# W511X.net
KiCad netlist of a schematic drawn in EAGLE
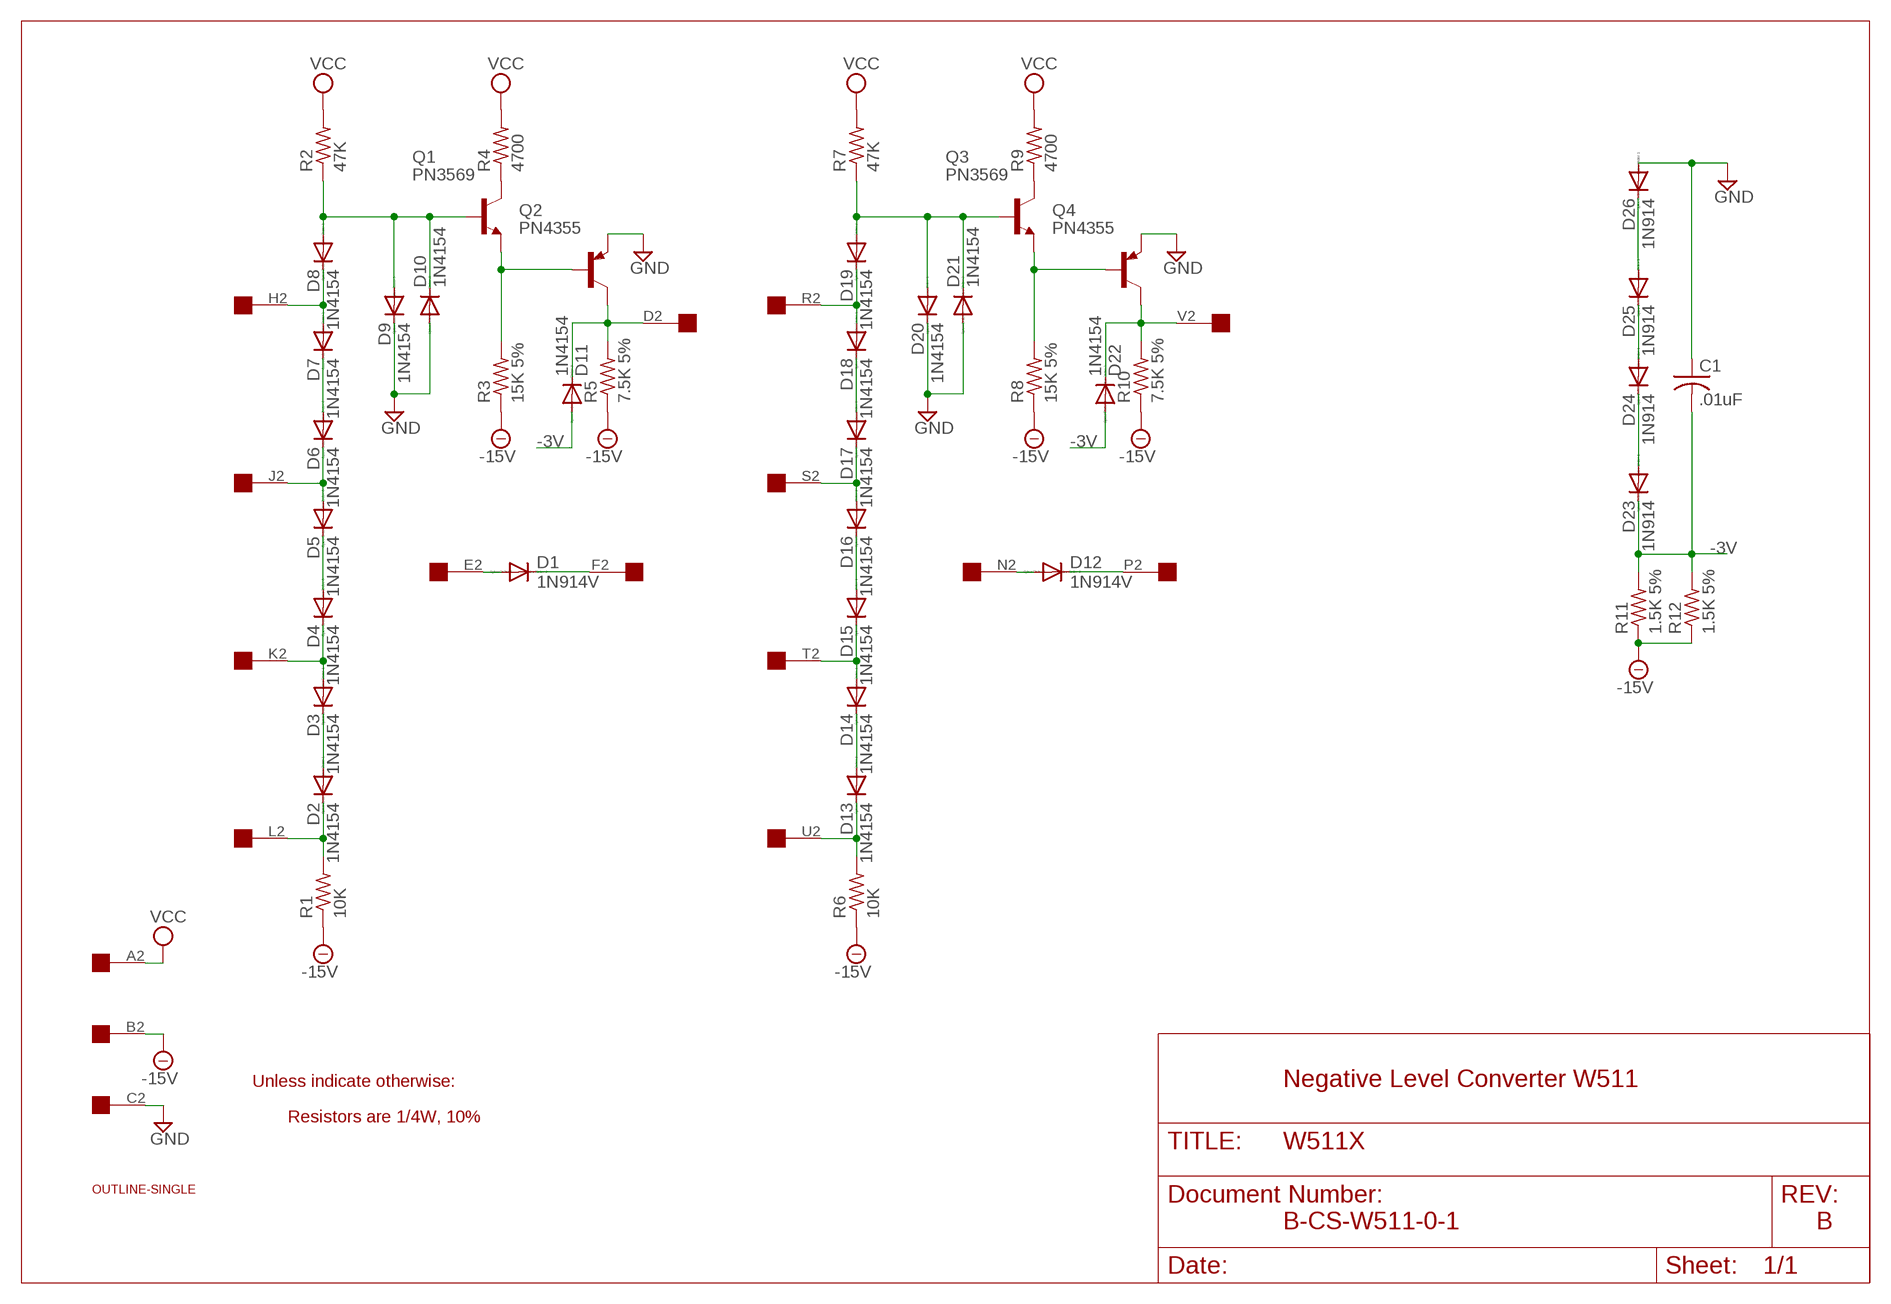
[diagram p0: schematic, sheet 1]

(export (version "E")
  (design (tool "Eeschema 10.0.6"))
  (components
    (comp (ref "C1")
      (value ".01uF")
      (footprint "eagle-import:C050-025X075")
      (libsource (lib "eagle-import") (part "C-US050-025X075"))
    )
    (comp (ref "D1")
      (value "1N914V")
      (footprint "eagle-import:DO35-10")
      (libsource (lib "eagle-import") (part "1N4148DO35-10"))
    )
    (comp (ref "D2")
      (value "1N4154")
      (footprint "eagle-import:DO35-10")
      (libsource (lib "eagle-import") (part "1N4148DO35-10"))
    )
    (comp (ref "D3")
      (value "1N4154")
      (footprint "eagle-import:DO35-10")
      (libsource (lib "eagle-import") (part "1N4148DO35-10"))
    )
    (comp (ref "D4")
      (value "1N4154")
      (footprint "eagle-import:DO35-10")
      (libsource (lib "eagle-import") (part "1N4148DO35-10"))
    )
    (comp (ref "D5")
      (value "1N4154")
      (footprint "eagle-import:DO35-10")
      (libsource (lib "eagle-import") (part "1N4148DO35-10"))
    )
    (comp (ref "D6")
      (value "1N4154")
      (footprint "eagle-import:DO35-10")
      (libsource (lib "eagle-import") (part "1N4148DO35-10"))
    )
    (comp (ref "D7")
      (value "1N4154")
      (footprint "eagle-import:DO35-10")
      (libsource (lib "eagle-import") (part "1N4148DO35-10"))
    )
    (comp (ref "D8")
      (value "1N4154")
      (footprint "eagle-import:DO35-10")
      (libsource (lib "eagle-import") (part "1N4148DO35-10"))
    )
    (comp (ref "D9")
      (value "1N4154")
      (footprint "eagle-import:DO35-10")
      (libsource (lib "eagle-import") (part "1N4148DO35-10"))
    )
    (comp (ref "D10")
      (value "1N4154")
      (footprint "eagle-import:DO35-10")
      (libsource (lib "eagle-import") (part "1N4148DO35-10"))
    )
    (comp (ref "D11")
      (value "1N4154")
      (footprint "eagle-import:DO35-10")
      (libsource (lib "eagle-import") (part "1N4148DO35-10"))
    )
    (comp (ref "D12")
      (value "1N914V")
      (footprint "eagle-import:DO35-10")
      (libsource (lib "eagle-import") (part "1N4148DO35-10"))
    )
    (comp (ref "D13")
      (value "1N4154")
      (footprint "eagle-import:DO35-10")
      (libsource (lib "eagle-import") (part "1N4148DO35-10"))
    )
    (comp (ref "D14")
      (value "1N4154")
      (footprint "eagle-import:DO35-10")
      (libsource (lib "eagle-import") (part "1N4148DO35-10"))
    )
    (comp (ref "D15")
      (value "1N4154")
      (footprint "eagle-import:DO35-10")
      (libsource (lib "eagle-import") (part "1N4148DO35-10"))
    )
    (comp (ref "D16")
      (value "1N4154")
      (footprint "eagle-import:DO35-10")
      (libsource (lib "eagle-import") (part "1N4148DO35-10"))
    )
    (comp (ref "D17")
      (value "1N4154")
      (footprint "eagle-import:DO35-10")
      (libsource (lib "eagle-import") (part "1N4148DO35-10"))
    )
    (comp (ref "D18")
      (value "1N4154")
      (footprint "eagle-import:DO35-10")
      (libsource (lib "eagle-import") (part "1N4148DO35-10"))
    )
    (comp (ref "D19")
      (value "1N4154")
      (footprint "eagle-import:DO35-10")
      (libsource (lib "eagle-import") (part "1N4148DO35-10"))
    )
    (comp (ref "D20")
      (value "1N4154")
      (footprint "eagle-import:DO35-10")
      (libsource (lib "eagle-import") (part "1N4148DO35-10"))
    )
    (comp (ref "D21")
      (value "1N4154")
      (footprint "eagle-import:DO35-10")
      (libsource (lib "eagle-import") (part "1N4148DO35-10"))
    )
    (comp (ref "D22")
      (value "1N4154")
      (footprint "eagle-import:DO35-10")
      (libsource (lib "eagle-import") (part "1N4148DO35-10"))
    )
    (comp (ref "D23")
      (value "1N914")
      (footprint "eagle-import:DO35-10")
      (libsource (lib "eagle-import") (part "1N4148DO35-10"))
    )
    (comp (ref "D24")
      (value "1N914")
      (footprint "eagle-import:DO35-10")
      (libsource (lib "eagle-import") (part "1N4148DO35-10"))
    )
    (comp (ref "D25")
      (value "1N914")
      (footprint "eagle-import:DO35-10")
      (libsource (lib "eagle-import") (part "1N4148DO35-10"))
    )
    (comp (ref "D26")
      (value "1N914")
      (footprint "eagle-import:DO35-10")
      (libsource (lib "eagle-import") (part "1N4148DO35-10"))
    )
    (comp (ref "EDGE")
      (value "EDGE-1")
      (footprint "eagle-import:EDGE-CON1")
      (libsource (lib "eagle-import") (part "EDGE-1"))
    )
    (comp (ref "Q1")
      (value "PN3569")
      (footprint "eagle-import:TO5")
      (libsource (lib "eagle-import") (part "2N2102"))
    )
    (comp (ref "Q2")
      (value "PN4355")
      (footprint "eagle-import:TO39")
      (libsource (lib "eagle-import") (part "2N2904"))
    )
    (comp (ref "Q3")
      (value "PN3569")
      (footprint "eagle-import:TO5")
      (libsource (lib "eagle-import") (part "2N2102"))
    )
    (comp (ref "Q4")
      (value "PN4355")
      (footprint "eagle-import:TO39")
      (libsource (lib "eagle-import") (part "2N2904"))
    )
    (comp (ref "R1")
      (value "10K")
      (footprint "eagle-import:0207_10")
      (libsource (lib "eagle-import") (part "R-US_0207/10"))
    )
    (comp (ref "R2")
      (value "47K")
      (footprint "eagle-import:0207_10")
      (libsource (lib "eagle-import") (part "R-US_0207/10"))
    )
    (comp (ref "R3")
      (value "15K 5%")
      (footprint "eagle-import:0207_10")
      (libsource (lib "eagle-import") (part "R-US_0207/10"))
    )
    (comp (ref "R4")
      (value "4700")
      (footprint "eagle-import:0207_10")
      (libsource (lib "eagle-import") (part "R-US_0207/10"))
    )
    (comp (ref "R5")
      (value "7.5K 5%")
      (footprint "eagle-import:0207_10")
      (libsource (lib "eagle-import") (part "R-US_0207/10"))
    )
    (comp (ref "R6")
      (value "10K")
      (footprint "eagle-import:0207_10")
      (libsource (lib "eagle-import") (part "R-US_0207/10"))
    )
    (comp (ref "R7")
      (value "47K")
      (footprint "eagle-import:0207_10")
      (libsource (lib "eagle-import") (part "R-US_0207/10"))
    )
    (comp (ref "R8")
      (value "15K 5%")
      (footprint "eagle-import:0207_10")
      (libsource (lib "eagle-import") (part "R-US_0207/10"))
    )
    (comp (ref "R9")
      (value "4700")
      (footprint "eagle-import:0207_10")
      (libsource (lib "eagle-import") (part "R-US_0207/10"))
    )
    (comp (ref "R10")
      (value "7.5K 5%")
      (footprint "eagle-import:0207_10")
      (libsource (lib "eagle-import") (part "R-US_0207/10"))
    )
    (comp (ref "R11")
      (value "1.5K 5%")
      (footprint "eagle-import:0207_10")
      (libsource (lib "eagle-import") (part "R-US_0207/10"))
    )
    (comp (ref "R12")
      (value "1.5K 5%")
      (footprint "eagle-import:0207_10")
      (libsource (lib "eagle-import") (part "R-US_0207/10"))
    )
    (comp (ref "U$1")
      (value "OUTLINE-SINGLE")
      (footprint "eagle-import:SINGLE")
      (libsource (lib "eagle-import") (part "OUTLINE-SINGLE"))
    )
  )
  (nets
    (net (code "1") (name "-15V") (class "Default")
      (node (ref "EDGE") (pin "B2") (pinfunction "1_B2") (pintype "bidirectional"))
      (node (ref "R1") (pin "1") (pinfunction "1_1") (pintype "passive"))
      (node (ref "R10") (pin "1") (pinfunction "1_1") (pintype "passive"))
      (node (ref "R11") (pin "1") (pinfunction "1_1") (pintype "passive"))
      (node (ref "R12") (pin "1") (pinfunction "1_1") (pintype "passive"))
      (node (ref "R3") (pin "1") (pinfunction "1_1") (pintype "passive"))
      (node (ref "R5") (pin "1") (pinfunction "1_1") (pintype "passive"))
      (node (ref "R6") (pin "1") (pinfunction "1_1") (pintype "passive"))
      (node (ref "R8") (pin "1") (pinfunction "1_1") (pintype "passive"))
    )
    (net (code "2") (name "/-3V") (class "Default")
      (node (ref "C1") (pin "2") (pinfunction "2_2") (pintype "passive"))
      (node (ref "D11") (pin "A") (pinfunction "A_A") (pintype "passive"))
      (node (ref "D22") (pin "A") (pinfunction "A_A") (pintype "passive"))
      (node (ref "D23") (pin "C") (pinfunction "C_C") (pintype "passive"))
      (node (ref "R11") (pin "2") (pinfunction "2_2") (pintype "passive"))
      (node (ref "R12") (pin "2") (pinfunction "2_2") (pintype "passive"))
    )
    (net (code "3") (name "GND") (class "Default")
      (node (ref "C1") (pin "1") (pinfunction "1_1") (pintype "passive"))
      (node (ref "D10") (pin "A") (pinfunction "A_A") (pintype "passive"))
      (node (ref "D20") (pin "C") (pinfunction "C_C") (pintype "passive"))
      (node (ref "D21") (pin "A") (pinfunction "A_A") (pintype "passive"))
      (node (ref "D26") (pin "A") (pinfunction "A_A") (pintype "passive"))
      (node (ref "D9") (pin "C") (pinfunction "C_C") (pintype "passive"))
      (node (ref "EDGE") (pin "C2") (pinfunction "1_C2") (pintype "bidirectional"))
      (node (ref "Q2") (pin "1") (pinfunction "E_1") (pintype "passive"))
      (node (ref "Q4") (pin "1") (pinfunction "E_1") (pintype "passive"))
    )
    (net (code "4") (name "Net-(D2-PadA)") (class "Default")
      (node (ref "D2") (pin "A") (pinfunction "A_A") (pintype "passive"))
      (node (ref "D3") (pin "C") (pinfunction "C_C") (pintype "passive"))
    )
    (net (code "5") (name "Net-(D4-PadA)") (class "Default")
      (node (ref "D4") (pin "A") (pinfunction "A_A") (pintype "passive"))
      (node (ref "D5") (pin "C") (pinfunction "C_C") (pintype "passive"))
    )
    (net (code "6") (name "Net-(D6-PadA)") (class "Default")
      (node (ref "D6") (pin "A") (pinfunction "A_A") (pintype "passive"))
      (node (ref "D7") (pin "C") (pinfunction "C_C") (pintype "passive"))
    )
    (net (code "7") (name "Net-(D13-PadA)") (class "Default")
      (node (ref "D13") (pin "A") (pinfunction "A_A") (pintype "passive"))
      (node (ref "D14") (pin "C") (pinfunction "C_C") (pintype "passive"))
    )
    (net (code "8") (name "Net-(D15-PadA)") (class "Default")
      (node (ref "D15") (pin "A") (pinfunction "A_A") (pintype "passive"))
      (node (ref "D16") (pin "C") (pinfunction "C_C") (pintype "passive"))
    )
    (net (code "9") (name "Net-(D17-PadA)") (class "Default")
      (node (ref "D17") (pin "A") (pinfunction "A_A") (pintype "passive"))
      (node (ref "D18") (pin "C") (pinfunction "C_C") (pintype "passive"))
    )
    (net (code "10") (name "Net-(D23-PadA)") (class "Default")
      (node (ref "D23") (pin "A") (pinfunction "A_A") (pintype "passive"))
      (node (ref "D24") (pin "C") (pinfunction "C_C") (pintype "passive"))
    )
    (net (code "11") (name "Net-(D24-PadA)") (class "Default")
      (node (ref "D24") (pin "A") (pinfunction "A_A") (pintype "passive"))
      (node (ref "D25") (pin "C") (pinfunction "C_C") (pintype "passive"))
    )
    (net (code "12") (name "Net-(D25-PadA)") (class "Default")
      (node (ref "D25") (pin "A") (pinfunction "A_A") (pintype "passive"))
      (node (ref "D26") (pin "C") (pinfunction "C_C") (pintype "passive"))
    )
    (net (code "13") (name "Net-(EDGED-1)") (class "Default")
      (node (ref "D11") (pin "C") (pinfunction "C_C") (pintype "passive"))
      (node (ref "EDGE") (pin "D2") (pinfunction "1_D2") (pintype "bidirectional"))
      (node (ref "Q2") (pin "3") (pinfunction "C_3") (pintype "passive"))
      (node (ref "R5") (pin "2") (pinfunction "2_2") (pintype "passive"))
    )
    (net (code "14") (name "Net-(EDGEE-1)") (class "Default")
      (node (ref "D1") (pin "A") (pinfunction "A_A") (pintype "passive"))
      (node (ref "EDGE") (pin "E2") (pinfunction "1_E2") (pintype "bidirectional"))
    )
    (net (code "15") (name "Net-(EDGEF-1)") (class "Default")
      (node (ref "D1") (pin "C") (pinfunction "C_C") (pintype "passive"))
      (node (ref "EDGE") (pin "F2") (pinfunction "1_F2") (pintype "bidirectional"))
    )
    (net (code "16") (name "Net-(EDGEG-1)") (class "Default")
      (node (ref "D7") (pin "A") (pinfunction "A_A") (pintype "passive"))
      (node (ref "D8") (pin "C") (pinfunction "C_C") (pintype "passive"))
      (node (ref "EDGE") (pin "H2") (pinfunction "1_H2") (pintype "bidirectional"))
    )
    (net (code "17") (name "Net-(EDGEH-1)") (class "Default")
      (node (ref "D5") (pin "A") (pinfunction "A_A") (pintype "passive"))
      (node (ref "D6") (pin "C") (pinfunction "C_C") (pintype "passive"))
      (node (ref "EDGE") (pin "J2") (pinfunction "1_J2") (pintype "bidirectional"))
    )
    (net (code "18") (name "Net-(EDGEI-1)") (class "Default")
      (node (ref "D3") (pin "A") (pinfunction "A_A") (pintype "passive"))
      (node (ref "D4") (pin "C") (pinfunction "C_C") (pintype "passive"))
      (node (ref "EDGE") (pin "K2") (pinfunction "1_K2") (pintype "bidirectional"))
    )
    (net (code "19") (name "Net-(EDGEJ-1)") (class "Default")
      (node (ref "D2") (pin "C") (pinfunction "C_C") (pintype "passive"))
      (node (ref "EDGE") (pin "L2") (pinfunction "1_L2") (pintype "bidirectional"))
      (node (ref "R1") (pin "2") (pinfunction "2_2") (pintype "passive"))
    )
    (net (code "20") (name "Net-(EDGEL-1)") (class "Default")
      (node (ref "D12") (pin "A") (pinfunction "A_A") (pintype "passive"))
      (node (ref "EDGE") (pin "N2") (pinfunction "1_N2") (pintype "bidirectional"))
    )
    (net (code "21") (name "Net-(EDGEM-1)") (class "Default")
      (node (ref "D12") (pin "C") (pinfunction "C_C") (pintype "passive"))
      (node (ref "EDGE") (pin "P2") (pinfunction "1_P2") (pintype "bidirectional"))
    )
    (net (code "22") (name "Net-(EDGEN-1)") (class "Default")
      (node (ref "D18") (pin "A") (pinfunction "A_A") (pintype "passive"))
      (node (ref "D19") (pin "C") (pinfunction "C_C") (pintype "passive"))
      (node (ref "EDGE") (pin "R2") (pinfunction "1_R2") (pintype "bidirectional"))
    )
    (net (code "23") (name "Net-(EDGEO-1)") (class "Default")
      (node (ref "D16") (pin "A") (pinfunction "A_A") (pintype "passive"))
      (node (ref "D17") (pin "C") (pinfunction "C_C") (pintype "passive"))
      (node (ref "EDGE") (pin "S2") (pinfunction "1_S2") (pintype "bidirectional"))
    )
    (net (code "24") (name "Net-(EDGEP-1)") (class "Default")
      (node (ref "D14") (pin "A") (pinfunction "A_A") (pintype "passive"))
      (node (ref "D15") (pin "C") (pinfunction "C_C") (pintype "passive"))
      (node (ref "EDGE") (pin "T2") (pinfunction "1_T2") (pintype "bidirectional"))
    )
    (net (code "25") (name "Net-(EDGEQ-1)") (class "Default")
      (node (ref "D13") (pin "C") (pinfunction "C_C") (pintype "passive"))
      (node (ref "EDGE") (pin "U2") (pinfunction "1_U2") (pintype "bidirectional"))
      (node (ref "R6") (pin "2") (pinfunction "2_2") (pintype "passive"))
    )
    (net (code "26") (name "Net-(EDGER-1)") (class "Default")
      (node (ref "D22") (pin "C") (pinfunction "C_C") (pintype "passive"))
      (node (ref "EDGE") (pin "V2") (pinfunction "1_V2") (pintype "bidirectional"))
      (node (ref "Q4") (pin "3") (pinfunction "C_3") (pintype "passive"))
      (node (ref "R10") (pin "2") (pinfunction "2_2") (pintype "passive"))
    )
    (net (code "27") (name "Net-(Q1-B)") (class "Default")
      (node (ref "D10") (pin "C") (pinfunction "C_C") (pintype "passive"))
      (node (ref "D8") (pin "A") (pinfunction "A_A") (pintype "passive"))
      (node (ref "D9") (pin "A") (pinfunction "A_A") (pintype "passive"))
      (node (ref "Q1") (pin "2") (pinfunction "B_2") (pintype "passive"))
      (node (ref "R2") (pin "1") (pinfunction "1_1") (pintype "passive"))
    )
    (net (code "28") (name "Net-(Q1-C)") (class "Default")
      (node (ref "Q1") (pin "3") (pinfunction "C_3") (pintype "passive"))
      (node (ref "R4") (pin "1") (pinfunction "1_1") (pintype "passive"))
    )
    (net (code "29") (name "Net-(Q1-E)") (class "Default")
      (node (ref "Q1") (pin "1") (pinfunction "E_1") (pintype "passive"))
      (node (ref "Q2") (pin "2") (pinfunction "B_2") (pintype "passive"))
      (node (ref "R3") (pin "2") (pinfunction "2_2") (pintype "passive"))
    )
    (net (code "30") (name "Net-(Q3-B)") (class "Default")
      (node (ref "D19") (pin "A") (pinfunction "A_A") (pintype "passive"))
      (node (ref "D20") (pin "A") (pinfunction "A_A") (pintype "passive"))
      (node (ref "D21") (pin "C") (pinfunction "C_C") (pintype "passive"))
      (node (ref "Q3") (pin "2") (pinfunction "B_2") (pintype "passive"))
      (node (ref "R7") (pin "1") (pinfunction "1_1") (pintype "passive"))
    )
    (net (code "31") (name "Net-(Q3-C)") (class "Default")
      (node (ref "Q3") (pin "3") (pinfunction "C_3") (pintype "passive"))
      (node (ref "R9") (pin "1") (pinfunction "1_1") (pintype "passive"))
    )
    (net (code "32") (name "Net-(Q3-E)") (class "Default")
      (node (ref "Q3") (pin "1") (pinfunction "E_1") (pintype "passive"))
      (node (ref "Q4") (pin "2") (pinfunction "B_2") (pintype "passive"))
      (node (ref "R8") (pin "2") (pinfunction "2_2") (pintype "passive"))
    )
    (net (code "33") (name "VCC") (class "Default")
      (node (ref "EDGE") (pin "A2") (pinfunction "1_A2") (pintype "bidirectional"))
      (node (ref "R2") (pin "2") (pinfunction "2_2") (pintype "passive"))
      (node (ref "R4") (pin "2") (pinfunction "2_2") (pintype "passive"))
      (node (ref "R7") (pin "2") (pinfunction "2_2") (pintype "passive"))
      (node (ref "R9") (pin "2") (pinfunction "2_2") (pintype "passive"))
    )
  )
)
